# Voltage_Logger.net
KiCad netlist of a schematic drawn in EAGLE
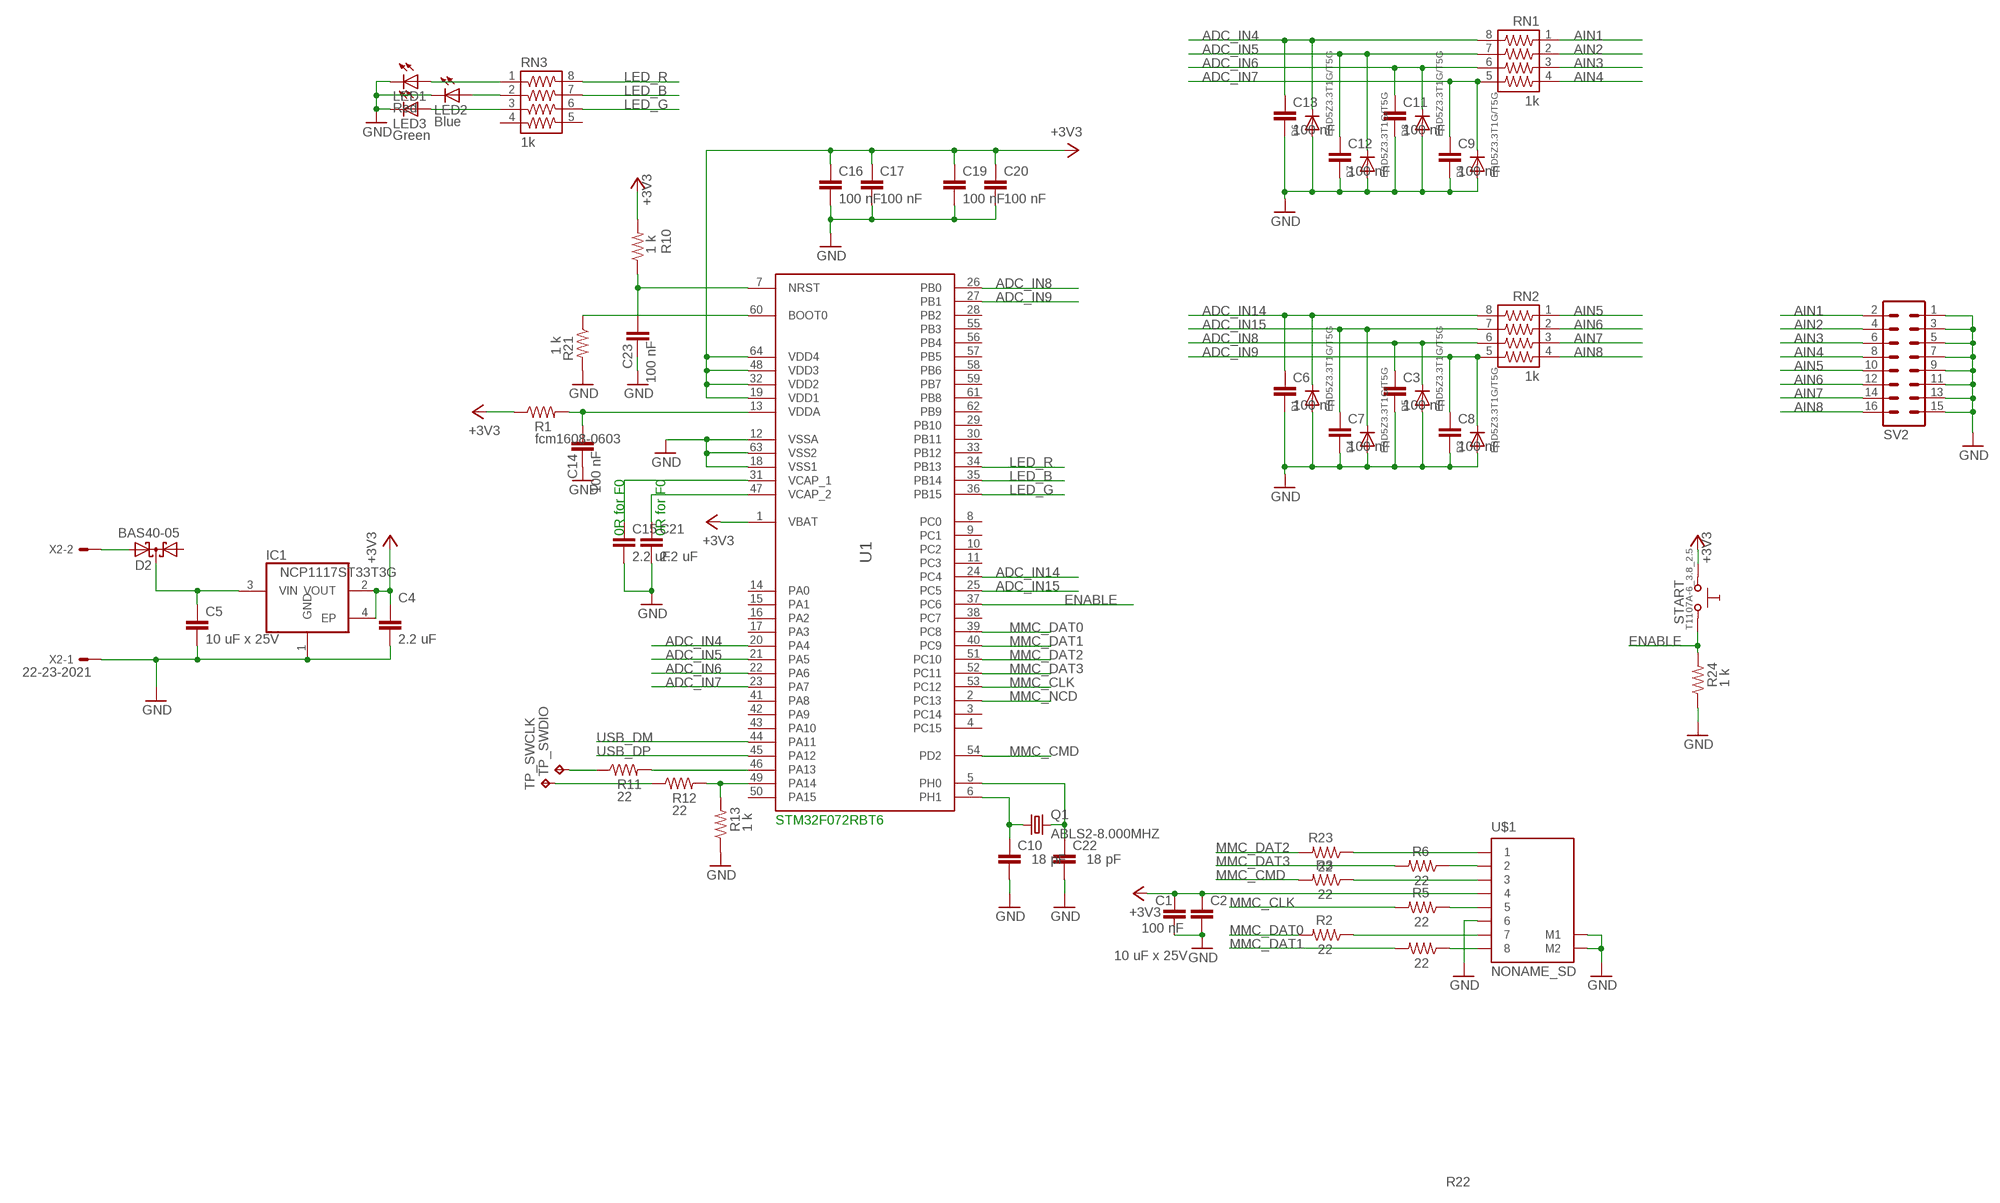
[diagram p0: schematic, sheet 1]

(export (version "E")
  (design (tool "Eeschema 10.0.6"))
  (components
    (comp (ref "C1")
      (value "100 nF")
      (footprint "eagle-import:C0603")
      (libsource (lib "eagle-import") (part "C-EUC0603"))
    )
    (comp (ref "C2")
      (value "10 uF x 25V")
      (footprint "eagle-import:C1206")
      (libsource (lib "eagle-import") (part "C-EUC1206"))
    )
    (comp (ref "C3")
      (value "100 nF")
      (footprint "eagle-import:C0603")
      (libsource (lib "eagle-import") (part "C-EUC0603"))
    )
    (comp (ref "C4")
      (value "2.2 uF")
      (footprint "eagle-import:C0603")
      (libsource (lib "eagle-import") (part "C-EUC0603"))
    )
    (comp (ref "C5")
      (value "10 uF x 25V")
      (footprint "eagle-import:C1206")
      (libsource (lib "eagle-import") (part "C-EUC1206"))
    )
    (comp (ref "C6")
      (value "100 nF")
      (footprint "eagle-import:C0603")
      (libsource (lib "eagle-import") (part "C-EUC0603"))
    )
    (comp (ref "C7")
      (value "100 nF")
      (footprint "eagle-import:C0603")
      (libsource (lib "eagle-import") (part "C-EUC0603"))
    )
    (comp (ref "C8")
      (value "100 nF")
      (footprint "eagle-import:C0603")
      (libsource (lib "eagle-import") (part "C-EUC0603"))
    )
    (comp (ref "C9")
      (value "100 nF")
      (footprint "eagle-import:C0603")
      (libsource (lib "eagle-import") (part "C-EUC0603"))
    )
    (comp (ref "C10")
      (value "18 pF")
      (footprint "eagle-import:C0603")
      (libsource (lib "eagle-import") (part "C-EUC0603"))
    )
    (comp (ref "C11")
      (value "100 nF")
      (footprint "eagle-import:C0603")
      (libsource (lib "eagle-import") (part "C-EUC0603"))
    )
    (comp (ref "C12")
      (value "100 nF")
      (footprint "eagle-import:C0603")
      (libsource (lib "eagle-import") (part "C-EUC0603"))
    )
    (comp (ref "C13")
      (value "100 nF")
      (footprint "eagle-import:C0603")
      (libsource (lib "eagle-import") (part "C-EUC0603"))
    )
    (comp (ref "C14")
      (value "100 nF")
      (footprint "eagle-import:C0603")
      (libsource (lib "eagle-import") (part "C-EUC0603"))
    )
    (comp (ref "C15")
      (value "2.2 uF")
      (footprint "eagle-import:C0603")
      (libsource (lib "eagle-import") (part "C-EUC0603"))
    )
    (comp (ref "C16")
      (value "100 nF")
      (footprint "eagle-import:C0603")
      (libsource (lib "eagle-import") (part "C-EUC0603"))
    )
    (comp (ref "C17")
      (value "100 nF")
      (footprint "eagle-import:C0603")
      (libsource (lib "eagle-import") (part "C-EUC0603"))
    )
    (comp (ref "C19")
      (value "100 nF")
      (footprint "eagle-import:C0603")
      (libsource (lib "eagle-import") (part "C-EUC0603"))
    )
    (comp (ref "C20")
      (value "100 nF")
      (footprint "eagle-import:C0603")
      (libsource (lib "eagle-import") (part "C-EUC0603"))
    )
    (comp (ref "C21")
      (value "2.2 uF")
      (footprint "eagle-import:C0603")
      (libsource (lib "eagle-import") (part "C-EUC0603"))
    )
    (comp (ref "C22")
      (value "18 pF")
      (footprint "eagle-import:C0603")
      (libsource (lib "eagle-import") (part "C-EUC0603"))
    )
    (comp (ref "C23")
      (value "100 nF")
      (footprint "eagle-import:C0603")
      (libsource (lib "eagle-import") (part "C-EUC0603"))
    )
    (comp (ref "D1")
      (value "ESD5Z3.3T1G/T5G")
      (footprint "eagle-import:SOD-523")
      (libsource (lib "eagle-import") (part "DIODESOD-523"))
    )
    (comp (ref "D2")
      (value "BAS40-05")
      (footprint "eagle-import:SOT23")
      (libsource (lib "eagle-import") (part "BAS40-05"))
    )
    (comp (ref "D3")
      (value "ESD5Z3.3T1G/T5G")
      (footprint "eagle-import:SOD-523")
      (libsource (lib "eagle-import") (part "DIODESOD-523"))
    )
    (comp (ref "D4")
      (value "ESD5Z3.3T1G/T5G")
      (footprint "eagle-import:SOD-523")
      (libsource (lib "eagle-import") (part "DIODESOD-523"))
    )
    (comp (ref "D5")
      (value "ESD5Z3.3T1G/T5G")
      (footprint "eagle-import:SOD-523")
      (libsource (lib "eagle-import") (part "DIODESOD-523"))
    )
    (comp (ref "D6")
      (value "ESD5Z3.3T1G/T5G")
      (footprint "eagle-import:SOD-523")
      (libsource (lib "eagle-import") (part "DIODESOD-523"))
    )
    (comp (ref "D7")
      (value "ESD5Z3.3T1G/T5G")
      (footprint "eagle-import:SOD-523")
      (libsource (lib "eagle-import") (part "DIODESOD-523"))
    )
    (comp (ref "D8")
      (value "ESD5Z3.3T1G/T5G")
      (footprint "eagle-import:SOD-523")
      (libsource (lib "eagle-import") (part "DIODESOD-523"))
    )
    (comp (ref "D9")
      (value "ESD5Z3.3T1G/T5G")
      (footprint "eagle-import:SOD-523")
      (libsource (lib "eagle-import") (part "DIODESOD-523"))
    )
    (comp (ref "IC1")
      (value "NCP1117ST33T3G")
      (footprint "eagle-import:SOT223")
      (fields (field (name "MPN") "REG1117"))
      (libsource (lib "eagle-import") (part "REG1117"))
    )
    (comp (ref "LED1")
      (value "Red")
      (footprint "eagle-import:LED_SML0603")
      (libsource (lib "eagle-import") (part "LED_ESML0603"))
    )
    (comp (ref "LED2")
      (value "Blue")
      (footprint "eagle-import:LED_SML0603")
      (libsource (lib "eagle-import") (part "LED_ESML0603"))
    )
    (comp (ref "LED3")
      (value "Green")
      (footprint "eagle-import:LED_SML0603")
      (libsource (lib "eagle-import") (part "LED_ESML0603"))
    )
    (comp (ref "Q1")
      (value "ABLS2-8.000MHZ")
      (footprint "eagle-import:SM49")
      (libsource (lib "eagle-import") (part "CRYSTALSM49"))
    )
    (comp (ref "R1")
      (value "fcm1608-0603")
      (footprint "eagle-import:R0603")
      (libsource (lib "eagle-import") (part "R-US_R0603"))
    )
    (comp (ref "R2")
      (value "22")
      (footprint "eagle-import:R0603")
      (libsource (lib "eagle-import") (part "R-US_R0603"))
    )
    (comp (ref "R3")
      (value "22")
      (footprint "eagle-import:R0603")
      (libsource (lib "eagle-import") (part "R-US_R0603"))
    )
    (comp (ref "R5")
      (value "22")
      (footprint "eagle-import:R0603")
      (libsource (lib "eagle-import") (part "R-US_R0603"))
    )
    (comp (ref "R6")
      (value "22")
      (footprint "eagle-import:R0603")
      (libsource (lib "eagle-import") (part "R-US_R0603"))
    )
    (comp (ref "R10")
      (value "1 k")
      (footprint "eagle-import:R0603")
      (libsource (lib "eagle-import") (part "R-US_R0603"))
    )
    (comp (ref "R11")
      (value "22")
      (footprint "eagle-import:R0603")
      (libsource (lib "eagle-import") (part "R-US_R0603"))
    )
    (comp (ref "R12")
      (value "22")
      (footprint "eagle-import:R0603")
      (libsource (lib "eagle-import") (part "R-US_R0603"))
    )
    (comp (ref "R13")
      (value "1 k")
      (footprint "eagle-import:R0603")
      (libsource (lib "eagle-import") (part "R-US_R0603"))
    )
    (comp (ref "R21")
      (value "1 k")
      (footprint "eagle-import:R0603")
      (libsource (lib "eagle-import") (part "R-US_R0603"))
    )
    (comp (ref "R22")
      (value "22")
      (footprint "eagle-import:R0603")
      (libsource (lib "eagle-import") (part "R-US_R0603"))
    )
    (comp (ref "R23")
      (value "22")
      (footprint "eagle-import:R0603")
      (libsource (lib "eagle-import") (part "R-US_R0603"))
    )
    (comp (ref "R24")
      (value "1 k")
      (footprint "eagle-import:R0603")
      (libsource (lib "eagle-import") (part "R-US_R0603"))
    )
    (comp (ref "RN1")
      (value "1k")
      (footprint "eagle-import:742-8NS")
      (libsource (lib "eagle-import") (part "742-8NS"))
    )
    (comp (ref "RN2")
      (value "1k")
      (footprint "eagle-import:742-8NS")
      (libsource (lib "eagle-import") (part "742-8NS"))
    )
    (comp (ref "RN3")
      (value "1k")
      (footprint "eagle-import:742-8NS")
      (libsource (lib "eagle-import") (part "742-8NS"))
    )
    (comp (ref "START")
      (value "T1107A-6_3.8_2.5")
      (footprint "eagle-import:SW-TAKT_6X3.5_SMD")
      (libsource (lib "eagle-import") (part "SW-TAKT6"))
    )
    (comp (ref "SV2")
      (value "MA08-2")
      (footprint "eagle-import:MA08-2")
      (libsource (lib "eagle-import") (part "MA08-2"))
    )
    (comp (ref "TP_SWCLK")
      (value "TPTP10SQ")
      (footprint "eagle-import:TP10SQ")
      (libsource (lib "eagle-import") (part "TPTP10SQ"))
    )
    (comp (ref "TP_SWDIO")
      (value "TPTP10SQ")
      (footprint "eagle-import:TP10SQ")
      (libsource (lib "eagle-import") (part "TPTP10SQ"))
    )
    (comp (ref "U$1")
      (value "NONAME_SD")
      (footprint "eagle-import:NONAME_SD")
      (libsource (lib "eagle-import") (part "NONAME_SD"))
    )
    (comp (ref "U1")
      (value "STM32F405RGT6")
      (footprint "eagle-import:LQFP64")
      (libsource (lib "eagle-import") (part "STM32F405XXSTM32F405XX"))
    )
    (comp (ref "X2")
      (value "22-23-2021")
      (footprint "eagle-import:22-23-2021")
      (fields (field (name "MF") "MOLEX"))
      (libsource (lib "eagle-import") (part "22-23-2021"))
    )
  )
  (nets
    (net (code "1") (name "+3V3") (class "Default")
      (node (ref "C1") (pin "1") (pinfunction "1_1") (pintype "passive"))
      (node (ref "C16") (pin "1") (pinfunction "1_1") (pintype "passive"))
      (node (ref "C17") (pin "1") (pinfunction "1_1") (pintype "passive"))
      (node (ref "C19") (pin "1") (pinfunction "1_1") (pintype "passive"))
      (node (ref "C2") (pin "1") (pinfunction "1_1") (pintype "passive"))
      (node (ref "C20") (pin "1") (pinfunction "1_1") (pintype "passive"))
      (node (ref "C4") (pin "1") (pinfunction "1_1") (pintype "passive"))
      (node (ref "IC1") (pin "2") (pinfunction "VOUT_2") (pintype "output"))
      (node (ref "IC1") (pin "4") (pinfunction "EP_4") (pintype "output"))
      (node (ref "R1") (pin "1") (pinfunction "1_1") (pintype "passive"))
      (node (ref "R10") (pin "2") (pinfunction "2_2") (pintype "passive"))
      (node (ref "START") (pin "P$1") (pinfunction "0_P$1") (pintype "passive"))
      (node (ref "U$1") (pin "4") (pinfunction "4_4") (pintype "input"))
      (node (ref "U1") (pin "1") (pinfunction "VBAT_1") (pintype "power_in"))
      (node (ref "U1") (pin "19") (pinfunction "VDD1_19") (pintype "power_in"))
      (node (ref "U1") (pin "32") (pinfunction "VDD2_32") (pintype "power_in"))
      (node (ref "U1") (pin "48") (pinfunction "VDD3_48") (pintype "power_in"))
      (node (ref "U1") (pin "64") (pinfunction "VDD4_64") (pintype "power_in"))
    )
    (net (code "2") (name "/ADC_IN4") (class "Default")
      (node (ref "C13") (pin "1") (pinfunction "1_1") (pintype "passive"))
      (node (ref "D6") (pin "K") (pinfunction "C_K") (pintype "passive"))
      (node (ref "RN1") (pin "8") (pinfunction "8_8") (pintype "passive"))
      (node (ref "U1") (pin "20") (pinfunction "PA4_20") (pintype "bidirectional"))
    )
    (net (code "3") (name "/ADC_IN5") (class "Default")
      (node (ref "C12") (pin "1") (pinfunction "1_1") (pintype "passive"))
      (node (ref "D7") (pin "K") (pinfunction "C_K") (pintype "passive"))
      (node (ref "RN1") (pin "7") (pinfunction "7_7") (pintype "passive"))
      (node (ref "U1") (pin "21") (pinfunction "PA5_21") (pintype "bidirectional"))
    )
    (net (code "4") (name "/ADC_IN6") (class "Default")
      (node (ref "C11") (pin "1") (pinfunction "1_1") (pintype "passive"))
      (node (ref "D8") (pin "K") (pinfunction "C_K") (pintype "passive"))
      (node (ref "RN1") (pin "6") (pinfunction "6_6") (pintype "passive"))
      (node (ref "U1") (pin "22") (pinfunction "PA6_22") (pintype "bidirectional"))
    )
    (net (code "5") (name "/ADC_IN7") (class "Default")
      (node (ref "C9") (pin "1") (pinfunction "1_1") (pintype "passive"))
      (node (ref "D9") (pin "K") (pinfunction "C_K") (pintype "passive"))
      (node (ref "RN1") (pin "5") (pinfunction "5_5") (pintype "passive"))
      (node (ref "U1") (pin "23") (pinfunction "PA7_23") (pintype "bidirectional"))
    )
    (net (code "6") (name "/ADC_IN8") (class "Default")
      (node (ref "C3") (pin "1") (pinfunction "1_1") (pintype "passive"))
      (node (ref "D5") (pin "K") (pinfunction "C_K") (pintype "passive"))
      (node (ref "RN2") (pin "6") (pinfunction "6_6") (pintype "passive"))
      (node (ref "U1") (pin "26") (pinfunction "PB0_26") (pintype "bidirectional"))
    )
    (net (code "7") (name "/ADC_IN9") (class "Default")
      (node (ref "C8") (pin "1") (pinfunction "1_1") (pintype "passive"))
      (node (ref "D3") (pin "K") (pinfunction "C_K") (pintype "passive"))
      (node (ref "RN2") (pin "5") (pinfunction "5_5") (pintype "passive"))
      (node (ref "U1") (pin "27") (pinfunction "PB1_27") (pintype "bidirectional"))
    )
    (net (code "8") (name "/ADC_IN14") (class "Default")
      (node (ref "C6") (pin "1") (pinfunction "1_1") (pintype "passive"))
      (node (ref "D1") (pin "K") (pinfunction "C_K") (pintype "passive"))
      (node (ref "RN2") (pin "8") (pinfunction "8_8") (pintype "passive"))
      (node (ref "U1") (pin "24") (pinfunction "PC4_24") (pintype "bidirectional"))
    )
    (net (code "9") (name "/ADC_IN15") (class "Default")
      (node (ref "C7") (pin "1") (pinfunction "1_1") (pintype "passive"))
      (node (ref "D4") (pin "K") (pinfunction "C_K") (pintype "passive"))
      (node (ref "RN2") (pin "7") (pinfunction "7_7") (pintype "passive"))
      (node (ref "U1") (pin "25") (pinfunction "PC5_25") (pintype "bidirectional"))
    )
    (net (code "10") (name "/AIN1") (class "Default")
      (node (ref "RN1") (pin "1") (pinfunction "1_1") (pintype "passive"))
      (node (ref "SV2") (pin "2") (pinfunction "2_2") (pintype "passive"))
    )
    (net (code "11") (name "/AIN2") (class "Default")
      (node (ref "RN1") (pin "2") (pinfunction "2_2") (pintype "passive"))
      (node (ref "SV2") (pin "4") (pinfunction "4_4") (pintype "passive"))
    )
    (net (code "12") (name "/AIN3") (class "Default")
      (node (ref "RN1") (pin "3") (pinfunction "3_3") (pintype "passive"))
      (node (ref "SV2") (pin "6") (pinfunction "6_6") (pintype "passive"))
    )
    (net (code "13") (name "/AIN4") (class "Default")
      (node (ref "RN1") (pin "4") (pinfunction "4_4") (pintype "passive"))
      (node (ref "SV2") (pin "8") (pinfunction "8_8") (pintype "passive"))
    )
    (net (code "14") (name "/AIN5") (class "Default")
      (node (ref "RN2") (pin "1") (pinfunction "1_1") (pintype "passive"))
      (node (ref "SV2") (pin "10") (pinfunction "10_10") (pintype "passive"))
    )
    (net (code "15") (name "/AIN6") (class "Default")
      (node (ref "RN2") (pin "2") (pinfunction "2_2") (pintype "passive"))
      (node (ref "SV2") (pin "12") (pinfunction "12_12") (pintype "passive"))
    )
    (net (code "16") (name "/AIN7") (class "Default")
      (node (ref "RN2") (pin "3") (pinfunction "3_3") (pintype "passive"))
      (node (ref "SV2") (pin "14") (pinfunction "14_14") (pintype "passive"))
    )
    (net (code "17") (name "/AIN8") (class "Default")
      (node (ref "RN2") (pin "4") (pinfunction "4_4") (pintype "passive"))
      (node (ref "SV2") (pin "16") (pinfunction "16_16") (pintype "passive"))
    )
    (net (code "18") (name "/ENABLE") (class "Default")
      (node (ref "R24") (pin "2") (pinfunction "2_2") (pintype "passive"))
      (node (ref "START") (pin "P$2") (pinfunction "1_P$2") (pintype "passive"))
      (node (ref "U1") (pin "37") (pinfunction "PC6_37") (pintype "bidirectional"))
    )
    (net (code "19") (name "/LED_B") (class "Default")
      (node (ref "RN3") (pin "7") (pinfunction "7_7") (pintype "passive"))
      (node (ref "U1") (pin "35") (pinfunction "PB14_35") (pintype "bidirectional"))
    )
    (net (code "20") (name "/LED_G") (class "Default")
      (node (ref "RN3") (pin "6") (pinfunction "6_6") (pintype "passive"))
      (node (ref "U1") (pin "36") (pinfunction "PB15_36") (pintype "bidirectional"))
    )
    (net (code "21") (name "/LED_R") (class "Default")
      (node (ref "RN3") (pin "8") (pinfunction "8_8") (pintype "passive"))
      (node (ref "U1") (pin "34") (pinfunction "PB13_34") (pintype "bidirectional"))
    )
    (net (code "22") (name "/MMC_CLK") (class "Default")
      (node (ref "R5") (pin "2") (pinfunction "2_2") (pintype "passive"))
      (node (ref "U1") (pin "53") (pinfunction "PC12_53") (pintype "bidirectional"))
    )
    (net (code "23") (name "/MMC_CMD") (class "Default")
      (node (ref "R3") (pin "2") (pinfunction "2_2") (pintype "passive"))
      (node (ref "U1") (pin "54") (pinfunction "PD2_54") (pintype "bidirectional"))
    )
    (net (code "24") (name "/MMC_DAT0") (class "Default")
      (node (ref "R2") (pin "2") (pinfunction "2_2") (pintype "passive"))
      (node (ref "U1") (pin "39") (pinfunction "PC8_39") (pintype "bidirectional"))
    )
    (net (code "25") (name "/MMC_DAT1") (class "Default")
      (node (ref "R22") (pin "2") (pinfunction "2_2") (pintype "passive"))
      (node (ref "U1") (pin "40") (pinfunction "PC9_40") (pintype "bidirectional"))
    )
    (net (code "26") (name "/MMC_DAT2") (class "Default")
      (node (ref "R23") (pin "2") (pinfunction "2_2") (pintype "passive"))
      (node (ref "U1") (pin "51") (pinfunction "PC10_51") (pintype "bidirectional"))
    )
    (net (code "27") (name "/MMC_DAT3") (class "Default")
      (node (ref "R6") (pin "2") (pinfunction "2_2") (pintype "passive"))
      (node (ref "U1") (pin "52") (pinfunction "PC11_52") (pintype "bidirectional"))
    )
    (net (code "28") (name "/MMC_NCD") (class "Default")
      (node (ref "U1") (pin "2") (pinfunction "PC13_2") (pintype "bidirectional"))
    )
    (net (code "29") (name "/USB_DM") (class "Default")
      (node (ref "U1") (pin "44") (pinfunction "PA11_44") (pintype "bidirectional"))
    )
    (net (code "30") (name "/USB_DP") (class "Default")
      (node (ref "U1") (pin "45") (pinfunction "PA12_45") (pintype "bidirectional"))
    )
    (net (code "31") (name "GND") (class "Default")
      (node (ref "C1") (pin "2") (pinfunction "2_2") (pintype "passive"))
      (node (ref "C10") (pin "2") (pinfunction "2_2") (pintype "passive"))
      (node (ref "C11") (pin "2") (pinfunction "2_2") (pintype "passive"))
      (node (ref "C12") (pin "2") (pinfunction "2_2") (pintype "passive"))
      (node (ref "C13") (pin "2") (pinfunction "2_2") (pintype "passive"))
      (node (ref "C14") (pin "2") (pinfunction "2_2") (pintype "passive"))
      (node (ref "C15") (pin "2") (pinfunction "2_2") (pintype "passive"))
      (node (ref "C16") (pin "2") (pinfunction "2_2") (pintype "passive"))
      (node (ref "C17") (pin "2") (pinfunction "2_2") (pintype "passive"))
      (node (ref "C19") (pin "2") (pinfunction "2_2") (pintype "passive"))
      (node (ref "C2") (pin "2") (pinfunction "2_2") (pintype "passive"))
      (node (ref "C20") (pin "2") (pinfunction "2_2") (pintype "passive"))
      (node (ref "C21") (pin "2") (pinfunction "2_2") (pintype "passive"))
      (node (ref "C22") (pin "2") (pinfunction "2_2") (pintype "passive"))
      (node (ref "C23") (pin "2") (pinfunction "2_2") (pintype "passive"))
      (node (ref "C3") (pin "2") (pinfunction "2_2") (pintype "passive"))
      (node (ref "C4") (pin "2") (pinfunction "2_2") (pintype "passive"))
      (node (ref "C5") (pin "2") (pinfunction "2_2") (pintype "passive"))
      (node (ref "C6") (pin "2") (pinfunction "2_2") (pintype "passive"))
      (node (ref "C7") (pin "2") (pinfunction "2_2") (pintype "passive"))
      (node (ref "C8") (pin "2") (pinfunction "2_2") (pintype "passive"))
      (node (ref "C9") (pin "2") (pinfunction "2_2") (pintype "passive"))
      (node (ref "D1") (pin "A") (pinfunction "A_A") (pintype "passive"))
      (node (ref "D3") (pin "A") (pinfunction "A_A") (pintype "passive"))
      (node (ref "D4") (pin "A") (pinfunction "A_A") (pintype "passive"))
      (node (ref "D5") (pin "A") (pinfunction "A_A") (pintype "passive"))
      (node (ref "D6") (pin "A") (pinfunction "A_A") (pintype "passive"))
      (node (ref "D7") (pin "A") (pinfunction "A_A") (pintype "passive"))
      (node (ref "D8") (pin "A") (pinfunction "A_A") (pintype "passive"))
      (node (ref "D9") (pin "A") (pinfunction "A_A") (pintype "passive"))
      (node (ref "IC1") (pin "1") (pinfunction "GND_1") (pintype "power_in"))
      (node (ref "LED1") (pin "C") (pinfunction "C_C") (pintype "passive"))
      (node (ref "LED2") (pin "C") (pinfunction "C_C") (pintype "passive"))
      (node (ref "LED3") (pin "C") (pinfunction "C_C") (pintype "passive"))
      (node (ref "R13") (pin "1") (pinfunction "1_1") (pintype "passive"))
      (node (ref "R21") (pin "2") (pinfunction "2_2") (pintype "passive"))
      (node (ref "R24") (pin "1") (pinfunction "1_1") (pintype "passive"))
      (node (ref "SV2") (pin "1") (pinfunction "1_1") (pintype "passive"))
      (node (ref "SV2") (pin "11") (pinfunction "11_11") (pintype "passive"))
      (node (ref "SV2") (pin "13") (pinfunction "13_13") (pintype "passive"))
      (node (ref "SV2") (pin "15") (pinfunction "15_15") (pintype "passive"))
      (node (ref "SV2") (pin "3") (pinfunction "3_3") (pintype "passive"))
      (node (ref "SV2") (pin "5") (pinfunction "5_5") (pintype "passive"))
      (node (ref "SV2") (pin "7") (pinfunction "7_7") (pintype "passive"))
      (node (ref "SV2") (pin "9") (pinfunction "9_9") (pintype "passive"))
      (node (ref "U$1") (pin "6") (pinfunction "6_6") (pintype "input"))
      (node (ref "U$1") (pin "M1") (pinfunction "M1_M1") (pintype "input"))
      (node (ref "U$1") (pin "M2") (pinfunction "M2_M2") (pintype "input"))
      (node (ref "U1") (pin "12") (pinfunction "VSSA_12") (pintype "power_in"))
      (node (ref "U1") (pin "18") (pinfunction "VSS1_18") (pintype "power_in"))
      (node (ref "U1") (pin "63") (pinfunction "VSS2_63") (pintype "power_in"))
      (node (ref "X2") (pin "1") (pinfunction "S_1") (pintype "passive"))
    )
    (net (code "32") (name "Net-(D2-A2)") (class "Default")
      (node (ref "D2") (pin "2") (pinfunction "A2_2") (pintype "passive"))
      (node (ref "X2") (pin "2") (pinfunction "S_2") (pintype "passive"))
    )
    (net (code "33") (name "Net-(D2-C)") (class "Default")
      (node (ref "C5") (pin "1") (pinfunction "1_1") (pintype "passive"))
      (node (ref "D2") (pin "3") (pinfunction "C_3") (pintype "passive"))
      (node (ref "IC1") (pin "3") (pinfunction "VIN_3") (pintype "input"))
    )
    (net (code "34") (name "Net-(LED1-PadA)") (class "Default")
      (node (ref "LED1") (pin "A") (pinfunction "A_A") (pintype "passive"))
      (node (ref "RN3") (pin "1") (pinfunction "1_1") (pintype "passive"))
    )
    (net (code "35") (name "Net-(LED2-PadA)") (class "Default")
      (node (ref "LED2") (pin "A") (pinfunction "A_A") (pintype "passive"))
      (node (ref "RN3") (pin "2") (pinfunction "2_2") (pintype "passive"))
    )
    (net (code "36") (name "Net-(LED3-PadA)") (class "Default")
      (node (ref "LED3") (pin "A") (pinfunction "A_A") (pintype "passive"))
      (node (ref "RN3") (pin "3") (pinfunction "3_3") (pintype "passive"))
    )
    (net (code "37") (name "Net-(R2-Pad1)") (class "Default")
      (node (ref "R2") (pin "1") (pinfunction "1_1") (pintype "passive"))
      (node (ref "U$1") (pin "7") (pinfunction "7_7") (pintype "input"))
    )
    (net (code "38") (name "Net-(R3-Pad1)") (class "Default")
      (node (ref "R3") (pin "1") (pinfunction "1_1") (pintype "passive"))
      (node (ref "U$1") (pin "3") (pinfunction "3_3") (pintype "input"))
    )
    (net (code "39") (name "Net-(R5-Pad1)") (class "Default")
      (node (ref "R5") (pin "1") (pinfunction "1_1") (pintype "passive"))
      (node (ref "U$1") (pin "5") (pinfunction "5_5") (pintype "input"))
    )
    (net (code "40") (name "Net-(R6-Pad1)") (class "Default")
      (node (ref "R6") (pin "1") (pinfunction "1_1") (pintype "passive"))
      (node (ref "U$1") (pin "2") (pinfunction "2_2") (pintype "input"))
    )
    (net (code "41") (name "Net-(R11-Pad1)") (class "Default")
      (node (ref "R11") (pin "1") (pinfunction "1_1") (pintype "passive"))
      (node (ref "TP_SWDIO") (pin "TP") (pinfunction "TP_TP") (pintype "input"))
    )
    (net (code "42") (name "Net-(R12-Pad1)") (class "Default")
      (node (ref "R12") (pin "1") (pinfunction "1_1") (pintype "passive"))
      (node (ref "TP_SWCLK") (pin "TP") (pinfunction "TP_TP") (pintype "input"))
    )
    (net (code "43") (name "Net-(R22-Pad1)") (class "Default")
      (node (ref "R22") (pin "1") (pinfunction "1_1") (pintype "passive"))
      (node (ref "U$1") (pin "8") (pinfunction "8_8") (pintype "input"))
    )
    (net (code "44") (name "Net-(R23-Pad1)") (class "Default")
      (node (ref "R23") (pin "1") (pinfunction "1_1") (pintype "passive"))
      (node (ref "U$1") (pin "1") (pinfunction "1_1") (pintype "input"))
    )
    (net (code "45") (name "Net-(U1-BOOT0)") (class "Default")
      (node (ref "R21") (pin "1") (pinfunction "1_1") (pintype "passive"))
      (node (ref "U1") (pin "60") (pinfunction "BOOT0_60") (pintype "bidirectional"))
    )
    (net (code "46") (name "Net-(U1-NRST)") (class "Default")
      (node (ref "C23") (pin "1") (pinfunction "1_1") (pintype "passive"))
      (node (ref "R10") (pin "1") (pinfunction "1_1") (pintype "passive"))
      (node (ref "U1") (pin "7") (pinfunction "NRST_7") (pintype "bidirectional"))
    )
    (net (code "47") (name "Net-(U1-PA13)") (class "Default")
      (node (ref "R11") (pin "2") (pinfunction "2_2") (pintype "passive"))
      (node (ref "U1") (pin "46") (pinfunction "PA13_46") (pintype "bidirectional"))
    )
    (net (code "48") (name "Net-(U1-PA14)") (class "Default")
      (node (ref "R12") (pin "2") (pinfunction "2_2") (pintype "passive"))
      (node (ref "R13") (pin "2") (pinfunction "2_2") (pintype "passive"))
      (node (ref "U1") (pin "49") (pinfunction "PA14_49") (pintype "bidirectional"))
    )
    (net (code "49") (name "Net-(U1-PH0)") (class "Default")
      (node (ref "C22") (pin "1") (pinfunction "1_1") (pintype "passive"))
      (node (ref "Q1") (pin "2") (pinfunction "2_2") (pintype "passive"))
      (node (ref "U1") (pin "5") (pinfunction "PH0_5") (pintype "bidirectional"))
    )
    (net (code "50") (name "Net-(U1-PH1)") (class "Default")
      (node (ref "C10") (pin "1") (pinfunction "1_1") (pintype "passive"))
      (node (ref "Q1") (pin "1") (pinfunction "1_1") (pintype "passive"))
      (node (ref "U1") (pin "6") (pinfunction "PH1_6") (pintype "bidirectional"))
    )
    (net (code "51") (name "Net-(U1-VCAP_1)") (class "Default")
      (node (ref "C15") (pin "1") (pinfunction "1_1") (pintype "passive"))
      (node (ref "U1") (pin "31") (pinfunction "VCAP_1_31") (pintype "power_in"))
    )
    (net (code "52") (name "Net-(U1-VCAP_2)") (class "Default")
      (node (ref "C21") (pin "1") (pinfunction "1_1") (pintype "passive"))
      (node (ref "U1") (pin "47") (pinfunction "VCAP_2_47") (pintype "power_in"))
    )
    (net (code "53") (name "Net-(U1-VDDA)") (class "Default")
      (node (ref "C14") (pin "1") (pinfunction "1_1") (pintype "passive"))
      (node (ref "R1") (pin "2") (pinfunction "2_2") (pintype "passive"))
      (node (ref "U1") (pin "13") (pinfunction "VDDA_13") (pintype "power_in"))
    )
    (net (code "54") (name "unconnected-(D2-A1-Pad1)") (class "Default")
      (node (ref "D2") (pin "1") (pinfunction "A1_1") (pintype "passive"))
    )
    (net (code "55") (name "unconnected-(RN3-Pad4)") (class "Default")
      (node (ref "RN3") (pin "4") (pinfunction "4_4") (pintype "passive"))
    )
    (net (code "56") (name "unconnected-(RN3-Pad5)") (class "Default")
      (node (ref "RN3") (pin "5") (pinfunction "5_5") (pintype "passive"))
    )
    (net (code "57") (name "unconnected-(U1-PA0-Pad14)") (class "Default")
      (node (ref "U1") (pin "14") (pinfunction "PA0_14") (pintype "bidirectional"))
    )
    (net (code "58") (name "unconnected-(U1-PA1-Pad15)") (class "Default")
      (node (ref "U1") (pin "15") (pinfunction "PA1_15") (pintype "bidirectional"))
    )
    (net (code "59") (name "unconnected-(U1-PA2-Pad16)") (class "Default")
      (node (ref "U1") (pin "16") (pinfunction "PA2_16") (pintype "bidirectional"))
    )
    (net (code "60") (name "unconnected-(U1-PA3-Pad17)") (class "Default")
      (node (ref "U1") (pin "17") (pinfunction "PA3_17") (pintype "bidirectional"))
    )
    (net (code "61") (name "unconnected-(U1-PA8-Pad41)") (class "Default")
      (node (ref "U1") (pin "41") (pinfunction "PA8_41") (pintype "bidirectional"))
    )
    (net (code "62") (name "unconnected-(U1-PA9-Pad42)") (class "Default")
      (node (ref "U1") (pin "42") (pinfunction "PA9_42") (pintype "bidirectional"))
    )
    (net (code "63") (name "unconnected-(U1-PA10-Pad43)") (class "Default")
      (node (ref "U1") (pin "43") (pinfunction "PA10_43") (pintype "bidirectional"))
    )
    (net (code "64") (name "unconnected-(U1-PA15-Pad50)") (class "Default")
      (node (ref "U1") (pin "50") (pinfunction "PA15_50") (pintype "bidirectional"))
    )
    (net (code "65") (name "unconnected-(U1-PB2-Pad28)") (class "Default")
      (node (ref "U1") (pin "28") (pinfunction "PB2_28") (pintype "bidirectional"))
    )
    (net (code "66") (name "unconnected-(U1-PB3-Pad55)") (class "Default")
      (node (ref "U1") (pin "55") (pinfunction "PB3_55") (pintype "bidirectional"))
    )
    (net (code "67") (name "unconnected-(U1-PB4-Pad56)") (class "Default")
      (node (ref "U1") (pin "56") (pinfunction "PB4_56") (pintype "bidirectional"))
    )
    (net (code "68") (name "unconnected-(U1-PB5-Pad57)") (class "Default")
      (node (ref "U1") (pin "57") (pinfunction "PB5_57") (pintype "bidirectional"))
    )
    (net (code "69") (name "unconnected-(U1-PB6-Pad58)") (class "Default")
      (node (ref "U1") (pin "58") (pinfunction "PB6_58") (pintype "bidirectional"))
    )
    (net (code "70") (name "unconnected-(U1-PB7-Pad59)") (class "Default")
      (node (ref "U1") (pin "59") (pinfunction "PB7_59") (pintype "bidirectional"))
    )
    (net (code "71") (name "unconnected-(U1-PB8-Pad61)") (class "Default")
      (node (ref "U1") (pin "61") (pinfunction "PB8_61") (pintype "bidirectional"))
    )
    (net (code "72") (name "unconnected-(U1-PB9-Pad62)") (class "Default")
      (node (ref "U1") (pin "62") (pinfunction "PB9_62") (pintype "bidirectional"))
    )
    (net (code "73") (name "unconnected-(U1-PB10-Pad29)") (class "Default")
      (node (ref "U1") (pin "29") (pinfunction "PB10_29") (pintype "bidirectional"))
    )
    (net (code "74") (name "unconnected-(U1-PB11-Pad30)") (class "Default")
      (node (ref "U1") (pin "30") (pinfunction "PB11_30") (pintype "bidirectional"))
    )
    (net (code "75") (name "unconnected-(U1-PB12-Pad33)") (class "Default")
      (node (ref "U1") (pin "33") (pinfunction "PB12_33") (pintype "bidirectional"))
    )
    (net (code "76") (name "unconnected-(U1-PC0-Pad8)") (class "Default")
      (node (ref "U1") (pin "8") (pinfunction "PC0_8") (pintype "bidirectional"))
    )
    (net (code "77") (name "unconnected-(U1-PC1-Pad9)") (class "Default")
      (node (ref "U1") (pin "9") (pinfunction "PC1_9") (pintype "bidirectional"))
    )
    (net (code "78") (name "unconnected-(U1-PC2-Pad10)") (class "Default")
      (node (ref "U1") (pin "10") (pinfunction "PC2_10") (pintype "bidirectional"))
    )
    (net (code "79") (name "unconnected-(U1-PC3-Pad11)") (class "Default")
      (node (ref "U1") (pin "11") (pinfunction "PC3_11") (pintype "bidirectional"))
    )
    (net (code "80") (name "unconnected-(U1-PC7-Pad38)") (class "Default")
      (node (ref "U1") (pin "38") (pinfunction "PC7_38") (pintype "bidirectional"))
    )
    (net (code "81") (name "unconnected-(U1-PC14-Pad3)") (class "Default")
      (node (ref "U1") (pin "3") (pinfunction "PC14_3") (pintype "bidirectional"))
    )
    (net (code "82") (name "unconnected-(U1-PC15-Pad4)") (class "Default")
      (node (ref "U1") (pin "4") (pinfunction "PC15_4") (pintype "bidirectional"))
    )
  )
)
